# WS2812BDriver.net
KiCad netlist of a schematic drawn in Altium Designer
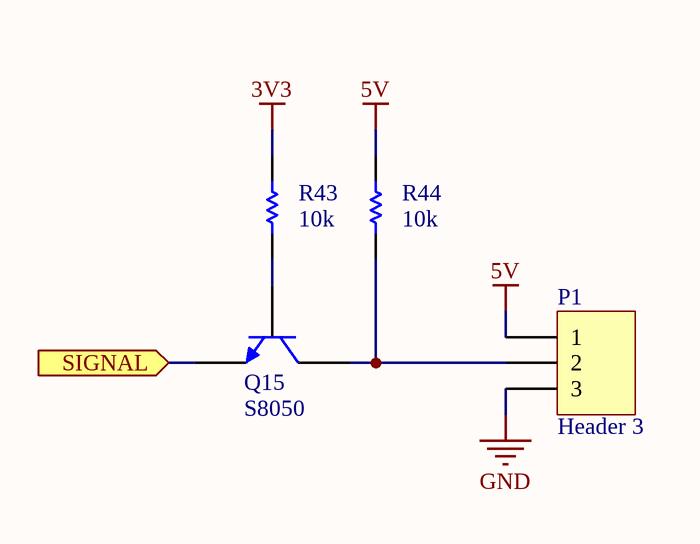
[diagram p0: WS2812BDriver.SchDoc]

(export (version "E")
  (design (tool "Eeschema 10.0.6"))
  (components
    (comp (ref "P1")
      (value "Header 3")
      (footprint "HDR1X3")
      (description "Header, 3-Pin")
      (fields (field (name "PUBLISHER") "Altium Limited"))
      (libsource (lib "Miscellaneous Connectors") (part "Header 3"))
    )
    (comp (ref "Q15")
      (value "S8050")
      (footprint "SOT23-3M")
      (description "NPN General Purpose Amplifier")
      (fields (field (name "PUBLISHER") "Altium Limited"))
      (libsource (lib "sumo") (part "S8050"))
    )
    (comp (ref "R43")
      (value "10k")
      (footprint "J1-0603")
      (description "Resistor")
      (fields (field (name "Comment") "Res1") (field (name "PUBLISHER") "Altium Limited"))
      (libsource (lib "Miscellaneous Devices") (part "Res1"))
    )
    (comp (ref "R44")
      (value "10k")
      (footprint "J1-0603")
      (description "Resistor")
      (fields (field (name "Comment") "Res1") (field (name "PUBLISHER") "Altium Limited"))
      (libsource (lib "Miscellaneous Devices") (part "Res1"))
    )
  )
  (nets
    (net (code "1") (name "/SIGNAL") (class "Default")
      (node (ref "Q15") (pin "2") (pinfunction "E_2") (pintype "passive"))
    )
    (net (code "2") (name "3V3") (class "Default")
      (node (ref "R43") (pin "2") (pinfunction "2_2") (pintype "passive"))
    )
    (net (code "3") (name "5V") (class "Default")
      (node (ref "P1") (pin "1") (pinfunction "1_1") (pintype "passive"))
      (node (ref "R44") (pin "2") (pinfunction "2_2") (pintype "passive"))
    )
    (net (code "4") (name "GND") (class "Default")
      (node (ref "P1") (pin "3") (pinfunction "3_3") (pintype "passive"))
    )
    (net (code "5") (name "Net-(Q15-B)") (class "Default")
      (node (ref "Q15") (pin "1") (pinfunction "B_1") (pintype "passive"))
      (node (ref "R43") (pin "1") (pinfunction "1_1") (pintype "passive"))
    )
    (net (code "6") (name "Net-(Q15-C)") (class "Default")
      (node (ref "P1") (pin "2") (pinfunction "2_2") (pintype "passive"))
      (node (ref "Q15") (pin "3") (pinfunction "C_3") (pintype "passive"))
      (node (ref "R44") (pin "1") (pinfunction "1_1") (pintype "passive"))
    )
  )
)
